# StreamDeck.net
KiCad netlist of a schematic drawn in EAGLE
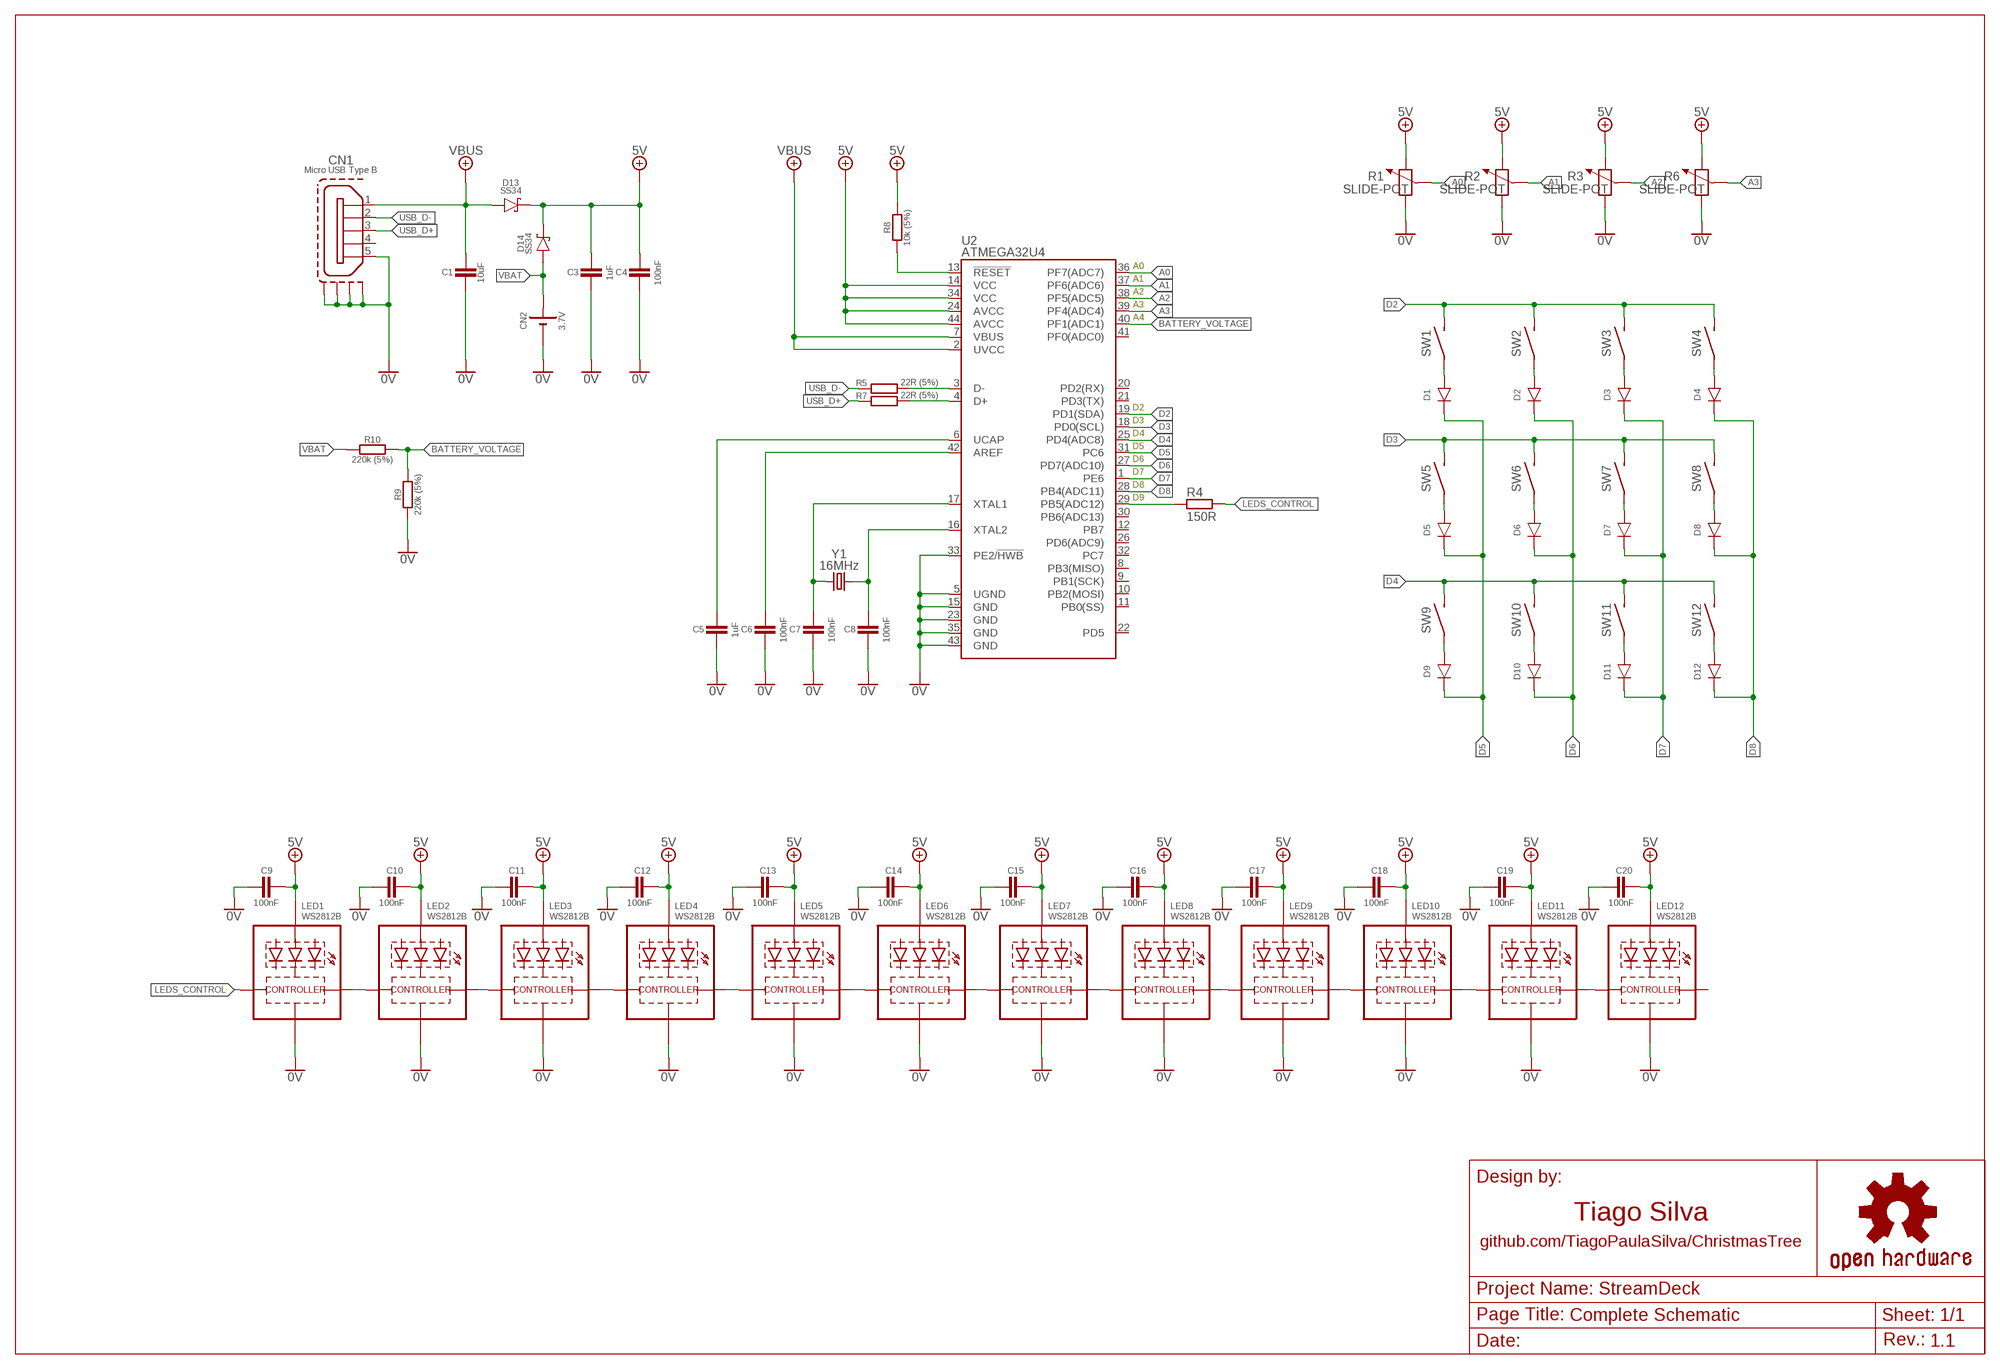
[diagram p0: schematic, sheet 1]

(export (version "E")
  (design (tool "Eeschema 10.0.6"))
  (components
    (comp (ref "C1")
      (value "10uF")
      (footprint "eagle-import:C0805")
      (libsource (lib "eagle-import") (part "C_0805"))
    )
    (comp (ref "C3")
      (value "1uF")
      (footprint "eagle-import:C0603")
      (libsource (lib "eagle-import") (part "C_0603"))
    )
    (comp (ref "C4")
      (value "100nF")
      (footprint "eagle-import:C0603")
      (libsource (lib "eagle-import") (part "C_0603"))
    )
    (comp (ref "C5")
      (value "1uF")
      (footprint "eagle-import:C0603")
      (libsource (lib "eagle-import") (part "C_0603"))
    )
    (comp (ref "C6")
      (value "100nF")
      (footprint "eagle-import:C0603")
      (libsource (lib "eagle-import") (part "C_0603"))
    )
    (comp (ref "C7")
      (value "100nF")
      (footprint "eagle-import:C0603")
      (libsource (lib "eagle-import") (part "C_0603"))
    )
    (comp (ref "C8")
      (value "100nF")
      (footprint "eagle-import:C0603")
      (libsource (lib "eagle-import") (part "C_0603"))
    )
    (comp (ref "C9")
      (value "100nF")
      (footprint "eagle-import:C0603")
      (libsource (lib "eagle-import") (part "C_0603"))
    )
    (comp (ref "C10")
      (value "100nF")
      (footprint "eagle-import:C0603")
      (libsource (lib "eagle-import") (part "C_0603"))
    )
    (comp (ref "C11")
      (value "100nF")
      (footprint "eagle-import:C0603")
      (libsource (lib "eagle-import") (part "C_0603"))
    )
    (comp (ref "C12")
      (value "100nF")
      (footprint "eagle-import:C0603")
      (libsource (lib "eagle-import") (part "C_0603"))
    )
    (comp (ref "C13")
      (value "100nF")
      (footprint "eagle-import:C0603")
      (libsource (lib "eagle-import") (part "C_0603"))
    )
    (comp (ref "C14")
      (value "100nF")
      (footprint "eagle-import:C0603")
      (libsource (lib "eagle-import") (part "C_0603"))
    )
    (comp (ref "C15")
      (value "100nF")
      (footprint "eagle-import:C0603")
      (libsource (lib "eagle-import") (part "C_0603"))
    )
    (comp (ref "C16")
      (value "100nF")
      (footprint "eagle-import:C0603")
      (libsource (lib "eagle-import") (part "C_0603"))
    )
    (comp (ref "C17")
      (value "100nF")
      (footprint "eagle-import:C0603")
      (libsource (lib "eagle-import") (part "C_0603"))
    )
    (comp (ref "C18")
      (value "100nF")
      (footprint "eagle-import:C0603")
      (libsource (lib "eagle-import") (part "C_0603"))
    )
    (comp (ref "C19")
      (value "100nF")
      (footprint "eagle-import:C0603")
      (libsource (lib "eagle-import") (part "C_0603"))
    )
    (comp (ref "C20")
      (value "100nF")
      (footprint "eagle-import:C0603")
      (libsource (lib "eagle-import") (part "C_0603"))
    )
    (comp (ref "CN1")
      (value "Micro USB Type B")
      (footprint "eagle-import:10118193-0001LF")
      (libsource (lib "eagle-import") (part "MICRO-USB"))
    )
    (comp (ref "CN2")
      (value "3.7V")
      (footprint "eagle-import:JST-PH2")
      (libsource (lib "eagle-import") (part "CELL-CONNECTOR"))
    )
    (comp (ref "D1")
      (value "LL4148")
      (footprint "eagle-import:SOD80")
      (libsource (lib "eagle-import") (part "LL4148"))
    )
    (comp (ref "D2")
      (value "LL4148")
      (footprint "eagle-import:SOD80")
      (libsource (lib "eagle-import") (part "LL4148"))
    )
    (comp (ref "D3")
      (value "LL4148")
      (footprint "eagle-import:SOD80")
      (libsource (lib "eagle-import") (part "LL4148"))
    )
    (comp (ref "D4")
      (value "LL4148")
      (footprint "eagle-import:SOD80")
      (libsource (lib "eagle-import") (part "LL4148"))
    )
    (comp (ref "D5")
      (value "LL4148")
      (footprint "eagle-import:SOD80")
      (libsource (lib "eagle-import") (part "LL4148"))
    )
    (comp (ref "D6")
      (value "LL4148")
      (footprint "eagle-import:SOD80")
      (libsource (lib "eagle-import") (part "LL4148"))
    )
    (comp (ref "D7")
      (value "LL4148")
      (footprint "eagle-import:SOD80")
      (libsource (lib "eagle-import") (part "LL4148"))
    )
    (comp (ref "D8")
      (value "LL4148")
      (footprint "eagle-import:SOD80")
      (libsource (lib "eagle-import") (part "LL4148"))
    )
    (comp (ref "D9")
      (value "LL4148")
      (footprint "eagle-import:SOD80")
      (libsource (lib "eagle-import") (part "LL4148"))
    )
    (comp (ref "D10")
      (value "LL4148")
      (footprint "eagle-import:SOD80")
      (libsource (lib "eagle-import") (part "LL4148"))
    )
    (comp (ref "D11")
      (value "LL4148")
      (footprint "eagle-import:SOD80")
      (libsource (lib "eagle-import") (part "LL4148"))
    )
    (comp (ref "D12")
      (value "LL4148")
      (footprint "eagle-import:SOD80")
      (libsource (lib "eagle-import") (part "LL4148"))
    )
    (comp (ref "D13")
      (value "SS34")
      (footprint "eagle-import:DO214AB")
      (libsource (lib "eagle-import") (part "SS34"))
    )
    (comp (ref "D14")
      (value "SS34")
      (footprint "eagle-import:DO214AB")
      (libsource (lib "eagle-import") (part "SS34"))
    )
    (comp (ref "LED1")
      (value "WS2812B")
      (footprint "eagle-import:5050")
      (libsource (lib "eagle-import") (part "WS2812B"))
    )
    (comp (ref "LED2")
      (value "WS2812B")
      (footprint "eagle-import:5050")
      (libsource (lib "eagle-import") (part "WS2812B"))
    )
    (comp (ref "LED3")
      (value "WS2812B")
      (footprint "eagle-import:5050")
      (libsource (lib "eagle-import") (part "WS2812B"))
    )
    (comp (ref "LED4")
      (value "WS2812B")
      (footprint "eagle-import:5050")
      (libsource (lib "eagle-import") (part "WS2812B"))
    )
    (comp (ref "LED5")
      (value "WS2812B")
      (footprint "eagle-import:5050")
      (libsource (lib "eagle-import") (part "WS2812B"))
    )
    (comp (ref "LED6")
      (value "WS2812B")
      (footprint "eagle-import:5050")
      (libsource (lib "eagle-import") (part "WS2812B"))
    )
    (comp (ref "LED7")
      (value "WS2812B")
      (footprint "eagle-import:5050")
      (libsource (lib "eagle-import") (part "WS2812B"))
    )
    (comp (ref "LED8")
      (value "WS2812B")
      (footprint "eagle-import:5050")
      (libsource (lib "eagle-import") (part "WS2812B"))
    )
    (comp (ref "LED9")
      (value "WS2812B")
      (footprint "eagle-import:5050")
      (libsource (lib "eagle-import") (part "WS2812B"))
    )
    (comp (ref "LED10")
      (value "WS2812B")
      (footprint "eagle-import:5050")
      (libsource (lib "eagle-import") (part "WS2812B"))
    )
    (comp (ref "LED11")
      (value "WS2812B")
      (footprint "eagle-import:5050")
      (libsource (lib "eagle-import") (part "WS2812B"))
    )
    (comp (ref "LED12")
      (value "WS2812B")
      (footprint "eagle-import:5050")
      (libsource (lib "eagle-import") (part "WS2812B"))
    )
    (comp (ref "R1")
      (value "SLIDE-POT")
      (footprint "eagle-import:SLIDER-75MM")
      (libsource (lib "eagle-import") (part "SLIDE-POT"))
    )
    (comp (ref "R2")
      (value "SLIDE-POT")
      (footprint "eagle-import:SLIDER-75MM")
      (libsource (lib "eagle-import") (part "SLIDE-POT"))
    )
    (comp (ref "R3")
      (value "SLIDE-POT")
      (footprint "eagle-import:SLIDER-75MM")
      (libsource (lib "eagle-import") (part "SLIDE-POT"))
    )
    (comp (ref "R4")
      (value "150R")
      (footprint "eagle-import:R0603")
      (libsource (lib "eagle-import") (part "R_0603"))
    )
    (comp (ref "R5")
      (value "22R (5%)")
      (footprint "eagle-import:R0603")
      (libsource (lib "eagle-import") (part "R_0603"))
    )
    (comp (ref "R6")
      (value "SLIDE-POT")
      (footprint "eagle-import:SLIDER-75MM")
      (libsource (lib "eagle-import") (part "SLIDE-POT"))
    )
    (comp (ref "R7")
      (value "22R (5%)")
      (footprint "eagle-import:R0603")
      (libsource (lib "eagle-import") (part "R_0603"))
    )
    (comp (ref "R8")
      (value "10k (5%)")
      (footprint "eagle-import:R0603")
      (libsource (lib "eagle-import") (part "R_0603"))
    )
    (comp (ref "R9")
      (value "220k (5%)")
      (footprint "eagle-import:R0603")
      (libsource (lib "eagle-import") (part "R_0603"))
    )
    (comp (ref "R10")
      (value "220k (5%)")
      (footprint "eagle-import:R0603")
      (libsource (lib "eagle-import") (part "R_0603"))
    )
    (comp (ref "SW1")
      (value "CHERRY_MX")
      (footprint "eagle-import:CHERRY-MX")
      (libsource (lib "eagle-import") (part "CHERRY_MX"))
    )
    (comp (ref "SW2")
      (value "CHERRY_MX")
      (footprint "eagle-import:CHERRY-MX")
      (libsource (lib "eagle-import") (part "CHERRY_MX"))
    )
    (comp (ref "SW3")
      (value "CHERRY_MX")
      (footprint "eagle-import:CHERRY-MX")
      (libsource (lib "eagle-import") (part "CHERRY_MX"))
    )
    (comp (ref "SW4")
      (value "CHERRY_MX")
      (footprint "eagle-import:CHERRY-MX")
      (libsource (lib "eagle-import") (part "CHERRY_MX"))
    )
    (comp (ref "SW5")
      (value "CHERRY_MX")
      (footprint "eagle-import:CHERRY-MX")
      (libsource (lib "eagle-import") (part "CHERRY_MX"))
    )
    (comp (ref "SW6")
      (value "CHERRY_MX")
      (footprint "eagle-import:CHERRY-MX")
      (libsource (lib "eagle-import") (part "CHERRY_MX"))
    )
    (comp (ref "SW7")
      (value "CHERRY_MX")
      (footprint "eagle-import:CHERRY-MX")
      (libsource (lib "eagle-import") (part "CHERRY_MX"))
    )
    (comp (ref "SW8")
      (value "CHERRY_MX")
      (footprint "eagle-import:CHERRY-MX")
      (libsource (lib "eagle-import") (part "CHERRY_MX"))
    )
    (comp (ref "SW9")
      (value "CHERRY_MX")
      (footprint "eagle-import:CHERRY-MX")
      (libsource (lib "eagle-import") (part "CHERRY_MX"))
    )
    (comp (ref "SW10")
      (value "CHERRY_MX")
      (footprint "eagle-import:CHERRY-MX")
      (libsource (lib "eagle-import") (part "CHERRY_MX"))
    )
    (comp (ref "SW11")
      (value "CHERRY_MX")
      (footprint "eagle-import:CHERRY-MX")
      (libsource (lib "eagle-import") (part "CHERRY_MX"))
    )
    (comp (ref "SW12")
      (value "CHERRY_MX")
      (footprint "eagle-import:CHERRY-MX")
      (libsource (lib "eagle-import") (part "CHERRY_MX"))
    )
    (comp (ref "U2")
      (value "ATMEGA32U4")
      (footprint "eagle-import:TESTING_QFN-44")
      (libsource (lib "eagle-import") (part "TESTING_ATMEGA32U4QFN"))
    )
    (comp (ref "Y1")
      (value "16MHz")
      (footprint "eagle-import:5.0X3.2_KX-9A")
      (libsource (lib "eagle-import") (part "KX-9A"))
    )
  )
  (nets
    (net (code "1") (name "0V") (class "Default")
      (node (ref "C1") (pin "2") (pinfunction "2_2") (pintype "passive"))
      (node (ref "C10") (pin "2") (pinfunction "2_2") (pintype "passive"))
      (node (ref "C11") (pin "2") (pinfunction "2_2") (pintype "passive"))
      (node (ref "C12") (pin "2") (pinfunction "2_2") (pintype "passive"))
      (node (ref "C13") (pin "2") (pinfunction "2_2") (pintype "passive"))
      (node (ref "C14") (pin "2") (pinfunction "2_2") (pintype "passive"))
      (node (ref "C15") (pin "2") (pinfunction "2_2") (pintype "passive"))
      (node (ref "C16") (pin "2") (pinfunction "2_2") (pintype "passive"))
      (node (ref "C17") (pin "2") (pinfunction "2_2") (pintype "passive"))
      (node (ref "C18") (pin "2") (pinfunction "2_2") (pintype "passive"))
      (node (ref "C19") (pin "2") (pinfunction "2_2") (pintype "passive"))
      (node (ref "C20") (pin "2") (pinfunction "2_2") (pintype "passive"))
      (node (ref "C3") (pin "2") (pinfunction "2_2") (pintype "passive"))
      (node (ref "C4") (pin "2") (pinfunction "2_2") (pintype "passive"))
      (node (ref "C5") (pin "2") (pinfunction "2_2") (pintype "passive"))
      (node (ref "C6") (pin "2") (pinfunction "2_2") (pintype "passive"))
      (node (ref "C7") (pin "2") (pinfunction "2_2") (pintype "passive"))
      (node (ref "C8") (pin "2") (pinfunction "2_2") (pintype "passive"))
      (node (ref "C9") (pin "2") (pinfunction "2_2") (pintype "passive"))
      (node (ref "CN1") (pin "5") (pinfunction "5_5") (pintype "passive"))
      (node (ref "CN1") (pin "MP1") (pinfunction "S1_MP1") (pintype "passive"))
      (node (ref "CN1") (pin "MP2") (pinfunction "S2_MP2") (pintype "passive"))
      (node (ref "CN1") (pin "MP3") (pinfunction "S3_MP3") (pintype "passive"))
      (node (ref "CN1") (pin "MP4") (pinfunction "S4_MP4") (pintype "passive"))
      (node (ref "CN2") (pin "2") (pinfunction "-_2") (pintype "passive"))
      (node (ref "LED1") (pin "3-GND") (pinfunction "GND_3-GND") (pintype "power_in"))
      (node (ref "LED10") (pin "3-GND") (pinfunction "GND_3-GND") (pintype "power_in"))
      (node (ref "LED11") (pin "3-GND") (pinfunction "GND_3-GND") (pintype "power_in"))
      (node (ref "LED12") (pin "3-GND") (pinfunction "GND_3-GND") (pintype "power_in"))
      (node (ref "LED2") (pin "3-GND") (pinfunction "GND_3-GND") (pintype "power_in"))
      (node (ref "LED3") (pin "3-GND") (pinfunction "GND_3-GND") (pintype "power_in"))
      (node (ref "LED4") (pin "3-GND") (pinfunction "GND_3-GND") (pintype "power_in"))
      (node (ref "LED5") (pin "3-GND") (pinfunction "GND_3-GND") (pintype "power_in"))
      (node (ref "LED6") (pin "3-GND") (pinfunction "GND_3-GND") (pintype "power_in"))
      (node (ref "LED7") (pin "3-GND") (pinfunction "GND_3-GND") (pintype "power_in"))
      (node (ref "LED8") (pin "3-GND") (pinfunction "GND_3-GND") (pintype "power_in"))
      (node (ref "LED9") (pin "3-GND") (pinfunction "GND_3-GND") (pintype "power_in"))
      (node (ref "R1") (pin "P$1") (pinfunction "1_P$1") (pintype "passive"))
      (node (ref "R2") (pin "P$1") (pinfunction "1_P$1") (pintype "passive"))
      (node (ref "R3") (pin "P$1") (pinfunction "1_P$1") (pintype "passive"))
      (node (ref "R6") (pin "P$1") (pinfunction "1_P$1") (pintype "passive"))
      (node (ref "R9") (pin "1") (pinfunction "1_1") (pintype "passive"))
      (node (ref "U2") (pin "15") (pinfunction "GND_15") (pintype "bidirectional"))
      (node (ref "U2") (pin "23") (pinfunction "GND_23") (pintype "bidirectional"))
      (node (ref "U2") (pin "33") (pinfunction "PE2/~{HWB}_33") (pintype "bidirectional"))
      (node (ref "U2") (pin "35") (pinfunction "GND_35") (pintype "bidirectional"))
      (node (ref "U2") (pin "43") (pinfunction "GND_43") (pintype "bidirectional"))
      (node (ref "U2") (pin "5") (pinfunction "UGND_5") (pintype "bidirectional"))
    )
    (net (code "2") (name "5V") (class "Default")
      (node (ref "C10") (pin "1") (pinfunction "1_1") (pintype "passive"))
      (node (ref "C11") (pin "1") (pinfunction "1_1") (pintype "passive"))
      (node (ref "C12") (pin "1") (pinfunction "1_1") (pintype "passive"))
      (node (ref "C13") (pin "1") (pinfunction "1_1") (pintype "passive"))
      (node (ref "C14") (pin "1") (pinfunction "1_1") (pintype "passive"))
      (node (ref "C15") (pin "1") (pinfunction "1_1") (pintype "passive"))
      (node (ref "C16") (pin "1") (pinfunction "1_1") (pintype "passive"))
      (node (ref "C17") (pin "1") (pinfunction "1_1") (pintype "passive"))
      (node (ref "C18") (pin "1") (pinfunction "1_1") (pintype "passive"))
      (node (ref "C19") (pin "1") (pinfunction "1_1") (pintype "passive"))
      (node (ref "C20") (pin "1") (pinfunction "1_1") (pintype "passive"))
      (node (ref "C3") (pin "1") (pinfunction "1_1") (pintype "passive"))
      (node (ref "C4") (pin "1") (pinfunction "1_1") (pintype "passive"))
      (node (ref "C9") (pin "1") (pinfunction "1_1") (pintype "passive"))
      (node (ref "D13") (pin "C") (pinfunction "K_C") (pintype "passive"))
      (node (ref "D14") (pin "C") (pinfunction "K_C") (pintype "passive"))
      (node (ref "LED1") (pin "1-VDD") (pinfunction "VDD_1-VDD") (pintype "power_in"))
      (node (ref "LED10") (pin "1-VDD") (pinfunction "VDD_1-VDD") (pintype "power_in"))
      (node (ref "LED11") (pin "1-VDD") (pinfunction "VDD_1-VDD") (pintype "power_in"))
      (node (ref "LED12") (pin "1-VDD") (pinfunction "VDD_1-VDD") (pintype "power_in"))
      (node (ref "LED2") (pin "1-VDD") (pinfunction "VDD_1-VDD") (pintype "power_in"))
      (node (ref "LED3") (pin "1-VDD") (pinfunction "VDD_1-VDD") (pintype "power_in"))
      (node (ref "LED4") (pin "1-VDD") (pinfunction "VDD_1-VDD") (pintype "power_in"))
      (node (ref "LED5") (pin "1-VDD") (pinfunction "VDD_1-VDD") (pintype "power_in"))
      (node (ref "LED6") (pin "1-VDD") (pinfunction "VDD_1-VDD") (pintype "power_in"))
      (node (ref "LED7") (pin "1-VDD") (pinfunction "VDD_1-VDD") (pintype "power_in"))
      (node (ref "LED8") (pin "1-VDD") (pinfunction "VDD_1-VDD") (pintype "power_in"))
      (node (ref "LED9") (pin "1-VDD") (pinfunction "VDD_1-VDD") (pintype "power_in"))
      (node (ref "R1") (pin "P$2") (pinfunction "2_P$2") (pintype "passive"))
      (node (ref "R2") (pin "P$2") (pinfunction "2_P$2") (pintype "passive"))
      (node (ref "R3") (pin "P$2") (pinfunction "2_P$2") (pintype "passive"))
      (node (ref "R6") (pin "P$2") (pinfunction "2_P$2") (pintype "passive"))
      (node (ref "R8") (pin "2") (pinfunction "2_2") (pintype "passive"))
      (node (ref "U2") (pin "14") (pinfunction "VCC_14") (pintype "bidirectional"))
      (node (ref "U2") (pin "24") (pinfunction "AVCC_24") (pintype "bidirectional"))
      (node (ref "U2") (pin "34") (pinfunction "VCC_34") (pintype "bidirectional"))
      (node (ref "U2") (pin "44") (pinfunction "AVCC_44") (pintype "bidirectional"))
    )
    (net (code "3") (name "A0") (class "Default")
      (node (ref "R1") (pin "P$6") (pinfunction "3_P$6") (pintype "passive"))
      (node (ref "U2") (pin "36") (pinfunction "PF7(ADC7)_36") (pintype "bidirectional"))
    )
    (net (code "4") (name "A1") (class "Default")
      (node (ref "R2") (pin "P$6") (pinfunction "3_P$6") (pintype "passive"))
      (node (ref "U2") (pin "37") (pinfunction "PF6(ADC6)_37") (pintype "bidirectional"))
    )
    (net (code "5") (name "A2") (class "Default")
      (node (ref "R3") (pin "P$6") (pinfunction "3_P$6") (pintype "passive"))
      (node (ref "U2") (pin "38") (pinfunction "PF5(ADC5)_38") (pintype "bidirectional"))
    )
    (net (code "6") (name "A3") (class "Default")
      (node (ref "R6") (pin "P$6") (pinfunction "3_P$6") (pintype "passive"))
      (node (ref "U2") (pin "39") (pinfunction "PF4(ADC4)_39") (pintype "bidirectional"))
    )
    (net (code "7") (name "BATTERY_VOLTAGE") (class "Default")
      (node (ref "R10") (pin "2") (pinfunction "2_2") (pintype "passive"))
      (node (ref "R9") (pin "2") (pinfunction "2_2") (pintype "passive"))
      (node (ref "U2") (pin "40") (pinfunction "PF1(ADC1)_40") (pintype "bidirectional"))
    )
    (net (code "8") (name "D2") (class "Default")
      (node (ref "SW1") (pin "SW2") (pinfunction "SW2_SW2") (pintype "passive"))
      (node (ref "SW2") (pin "SW2") (pinfunction "SW2_SW2") (pintype "passive"))
      (node (ref "SW3") (pin "SW2") (pinfunction "SW2_SW2") (pintype "passive"))
      (node (ref "SW4") (pin "SW2") (pinfunction "SW2_SW2") (pintype "passive"))
      (node (ref "U2") (pin "19") (pinfunction "PD1(SDA)_19") (pintype "bidirectional"))
    )
    (net (code "9") (name "D3") (class "Default")
      (node (ref "SW5") (pin "SW2") (pinfunction "SW2_SW2") (pintype "passive"))
      (node (ref "SW6") (pin "SW2") (pinfunction "SW2_SW2") (pintype "passive"))
      (node (ref "SW7") (pin "SW2") (pinfunction "SW2_SW2") (pintype "passive"))
      (node (ref "SW8") (pin "SW2") (pinfunction "SW2_SW2") (pintype "passive"))
      (node (ref "U2") (pin "18") (pinfunction "PD0(SCL)_18") (pintype "bidirectional"))
    )
    (net (code "10") (name "D4") (class "Default")
      (node (ref "SW10") (pin "SW2") (pinfunction "SW2_SW2") (pintype "passive"))
      (node (ref "SW11") (pin "SW2") (pinfunction "SW2_SW2") (pintype "passive"))
      (node (ref "SW12") (pin "SW2") (pinfunction "SW2_SW2") (pintype "passive"))
      (node (ref "SW9") (pin "SW2") (pinfunction "SW2_SW2") (pintype "passive"))
      (node (ref "U2") (pin "25") (pinfunction "PD4(ADC8)_25") (pintype "bidirectional"))
    )
    (net (code "11") (name "D5") (class "Default")
      (node (ref "D1") (pin "1") (pinfunction "K_1") (pintype "passive"))
      (node (ref "D5") (pin "1") (pinfunction "K_1") (pintype "passive"))
      (node (ref "D9") (pin "1") (pinfunction "K_1") (pintype "passive"))
      (node (ref "U2") (pin "31") (pinfunction "PC6_31") (pintype "bidirectional"))
    )
    (net (code "12") (name "D6") (class "Default")
      (node (ref "D10") (pin "1") (pinfunction "K_1") (pintype "passive"))
      (node (ref "D2") (pin "1") (pinfunction "K_1") (pintype "passive"))
      (node (ref "D6") (pin "1") (pinfunction "K_1") (pintype "passive"))
      (node (ref "U2") (pin "27") (pinfunction "PD7(ADC10)_27") (pintype "bidirectional"))
    )
    (net (code "13") (name "D7") (class "Default")
      (node (ref "D11") (pin "1") (pinfunction "K_1") (pintype "passive"))
      (node (ref "D3") (pin "1") (pinfunction "K_1") (pintype "passive"))
      (node (ref "D7") (pin "1") (pinfunction "K_1") (pintype "passive"))
      (node (ref "U2") (pin "1") (pinfunction "PE6_1") (pintype "bidirectional"))
    )
    (net (code "14") (name "D8") (class "Default")
      (node (ref "D12") (pin "1") (pinfunction "K_1") (pintype "passive"))
      (node (ref "D4") (pin "1") (pinfunction "K_1") (pintype "passive"))
      (node (ref "D8") (pin "1") (pinfunction "K_1") (pintype "passive"))
      (node (ref "U2") (pin "28") (pinfunction "PB4(ADC11)_28") (pintype "bidirectional"))
    )
    (net (code "15") (name "LEDS_CONTROL") (class "Default")
      (node (ref "LED1") (pin "4-DIN") (pinfunction "DI_4-DIN") (pintype "input"))
      (node (ref "R4") (pin "2") (pinfunction "2_2") (pintype "passive"))
    )
    (net (code "16") (name "Net-(D1-A)") (class "Default")
      (node (ref "D1") (pin "2") (pinfunction "A_2") (pintype "passive"))
      (node (ref "SW1") (pin "SW1") (pinfunction "SW1_SW1") (pintype "passive"))
    )
    (net (code "17") (name "Net-(D2-A)") (class "Default")
      (node (ref "D2") (pin "2") (pinfunction "A_2") (pintype "passive"))
      (node (ref "SW2") (pin "SW1") (pinfunction "SW1_SW1") (pintype "passive"))
    )
    (net (code "18") (name "Net-(D3-A)") (class "Default")
      (node (ref "D3") (pin "2") (pinfunction "A_2") (pintype "passive"))
      (node (ref "SW3") (pin "SW1") (pinfunction "SW1_SW1") (pintype "passive"))
    )
    (net (code "19") (name "Net-(D4-A)") (class "Default")
      (node (ref "D4") (pin "2") (pinfunction "A_2") (pintype "passive"))
      (node (ref "SW4") (pin "SW1") (pinfunction "SW1_SW1") (pintype "passive"))
    )
    (net (code "20") (name "Net-(D5-A)") (class "Default")
      (node (ref "D5") (pin "2") (pinfunction "A_2") (pintype "passive"))
      (node (ref "SW5") (pin "SW1") (pinfunction "SW1_SW1") (pintype "passive"))
    )
    (net (code "21") (name "Net-(D6-A)") (class "Default")
      (node (ref "D6") (pin "2") (pinfunction "A_2") (pintype "passive"))
      (node (ref "SW6") (pin "SW1") (pinfunction "SW1_SW1") (pintype "passive"))
    )
    (net (code "22") (name "Net-(D7-A)") (class "Default")
      (node (ref "D7") (pin "2") (pinfunction "A_2") (pintype "passive"))
      (node (ref "SW7") (pin "SW1") (pinfunction "SW1_SW1") (pintype "passive"))
    )
    (net (code "23") (name "Net-(D8-A)") (class "Default")
      (node (ref "D8") (pin "2") (pinfunction "A_2") (pintype "passive"))
      (node (ref "SW8") (pin "SW1") (pinfunction "SW1_SW1") (pintype "passive"))
    )
    (net (code "24") (name "Net-(D9-A)") (class "Default")
      (node (ref "D9") (pin "2") (pinfunction "A_2") (pintype "passive"))
      (node (ref "SW9") (pin "SW1") (pinfunction "SW1_SW1") (pintype "passive"))
    )
    (net (code "25") (name "Net-(D10-A)") (class "Default")
      (node (ref "D10") (pin "2") (pinfunction "A_2") (pintype "passive"))
      (node (ref "SW10") (pin "SW1") (pinfunction "SW1_SW1") (pintype "passive"))
    )
    (net (code "26") (name "Net-(D11-A)") (class "Default")
      (node (ref "D11") (pin "2") (pinfunction "A_2") (pintype "passive"))
      (node (ref "SW11") (pin "SW1") (pinfunction "SW1_SW1") (pintype "passive"))
    )
    (net (code "27") (name "Net-(D12-A)") (class "Default")
      (node (ref "D12") (pin "2") (pinfunction "A_2") (pintype "passive"))
      (node (ref "SW12") (pin "SW1") (pinfunction "SW1_SW1") (pintype "passive"))
    )
    (net (code "28") (name "Net-(LED1-DO)") (class "Default")
      (node (ref "LED1") (pin "2-DOUT") (pinfunction "DO_2-DOUT") (pintype "output"))
      (node (ref "LED2") (pin "4-DIN") (pinfunction "DI_4-DIN") (pintype "input"))
    )
    (net (code "29") (name "Net-(LED2-DO)") (class "Default")
      (node (ref "LED2") (pin "2-DOUT") (pinfunction "DO_2-DOUT") (pintype "output"))
      (node (ref "LED3") (pin "4-DIN") (pinfunction "DI_4-DIN") (pintype "input"))
    )
    (net (code "30") (name "Net-(LED3-DO)") (class "Default")
      (node (ref "LED3") (pin "2-DOUT") (pinfunction "DO_2-DOUT") (pintype "output"))
      (node (ref "LED4") (pin "4-DIN") (pinfunction "DI_4-DIN") (pintype "input"))
    )
    (net (code "31") (name "Net-(LED4-DO)") (class "Default")
      (node (ref "LED4") (pin "2-DOUT") (pinfunction "DO_2-DOUT") (pintype "output"))
      (node (ref "LED5") (pin "4-DIN") (pinfunction "DI_4-DIN") (pintype "input"))
    )
    (net (code "32") (name "Net-(LED5-DO)") (class "Default")
      (node (ref "LED5") (pin "2-DOUT") (pinfunction "DO_2-DOUT") (pintype "output"))
      (node (ref "LED6") (pin "4-DIN") (pinfunction "DI_4-DIN") (pintype "input"))
    )
    (net (code "33") (name "Net-(LED6-DO)") (class "Default")
      (node (ref "LED6") (pin "2-DOUT") (pinfunction "DO_2-DOUT") (pintype "output"))
      (node (ref "LED7") (pin "4-DIN") (pinfunction "DI_4-DIN") (pintype "input"))
    )
    (net (code "34") (name "Net-(LED7-DO)") (class "Default")
      (node (ref "LED7") (pin "2-DOUT") (pinfunction "DO_2-DOUT") (pintype "output"))
      (node (ref "LED8") (pin "4-DIN") (pinfunction "DI_4-DIN") (pintype "input"))
    )
    (net (code "35") (name "Net-(LED8-DO)") (class "Default")
      (node (ref "LED8") (pin "2-DOUT") (pinfunction "DO_2-DOUT") (pintype "output"))
      (node (ref "LED9") (pin "4-DIN") (pinfunction "DI_4-DIN") (pintype "input"))
    )
    (net (code "36") (name "Net-(LED10-DI)") (class "Default")
      (node (ref "LED10") (pin "4-DIN") (pinfunction "DI_4-DIN") (pintype "input"))
      (node (ref "LED9") (pin "2-DOUT") (pinfunction "DO_2-DOUT") (pintype "output"))
    )
    (net (code "37") (name "Net-(LED10-DO)") (class "Default")
      (node (ref "LED10") (pin "2-DOUT") (pinfunction "DO_2-DOUT") (pintype "output"))
      (node (ref "LED11") (pin "4-DIN") (pinfunction "DI_4-DIN") (pintype "input"))
    )
    (net (code "38") (name "Net-(LED11-DO)") (class "Default")
      (node (ref "LED11") (pin "2-DOUT") (pinfunction "DO_2-DOUT") (pintype "output"))
      (node (ref "LED12") (pin "4-DIN") (pinfunction "DI_4-DIN") (pintype "input"))
    )
    (net (code "39") (name "Net-(U2-AREF)") (class "Default")
      (node (ref "C6") (pin "1") (pinfunction "1_1") (pintype "passive"))
      (node (ref "U2") (pin "42") (pinfunction "AREF_42") (pintype "bidirectional"))
    )
    (net (code "40") (name "Net-(U2-D+)") (class "Default")
      (node (ref "R7") (pin "2") (pinfunction "2_2") (pintype "passive"))
      (node (ref "U2") (pin "4") (pinfunction "D+_4") (pintype "bidirectional"))
    )
    (net (code "41") (name "Net-(U2-D-)") (class "Default")
      (node (ref "R5") (pin "2") (pinfunction "2_2") (pintype "passive"))
      (node (ref "U2") (pin "3") (pinfunction "D-_3") (pintype "bidirectional"))
    )
    (net (code "42") (name "Net-(U2-PB5(ADC12))") (class "Default")
      (node (ref "R4") (pin "1") (pinfunction "1_1") (pintype "passive"))
      (node (ref "U2") (pin "29") (pinfunction "PB5(ADC12)_29") (pintype "bidirectional"))
    )
    (net (code "43") (name "Net-(U2-UCAP)") (class "Default")
      (node (ref "C5") (pin "1") (pinfunction "1_1") (pintype "passive"))
      (node (ref "U2") (pin "6") (pinfunction "UCAP_6") (pintype "bidirectional"))
    )
    (net (code "44") (name "Net-(U2-XTAL1)") (class "Default")
      (node (ref "C7") (pin "1") (pinfunction "1_1") (pintype "passive"))
      (node (ref "U2") (pin "17") (pinfunction "XTAL1_17") (pintype "bidirectional"))
      (node (ref "Y1") (pin "1") (pinfunction "1_1") (pintype "passive"))
    )
    (net (code "45") (name "Net-(U2-XTAL2)") (class "Default")
      (node (ref "C8") (pin "1") (pinfunction "1_1") (pintype "passive"))
      (node (ref "U2") (pin "16") (pinfunction "XTAL2_16") (pintype "bidirectional"))
      (node (ref "Y1") (pin "3") (pinfunction "2_3") (pintype "passive"))
    )
    (net (code "46") (name "Net-(U2-~{RESET})") (class "Default")
      (node (ref "R8") (pin "1") (pinfunction "1_1") (pintype "passive"))
      (node (ref "U2") (pin "13") (pinfunction "~{RESET}_13") (pintype "bidirectional"))
    )
    (net (code "47") (name "USB_D+") (class "Default")
      (node (ref "CN1") (pin "3") (pinfunction "3_3") (pintype "passive"))
      (node (ref "R7") (pin "1") (pinfunction "1_1") (pintype "passive"))
    )
    (net (code "48") (name "USB_D-") (class "Default")
      (node (ref "CN1") (pin "2") (pinfunction "2_2") (pintype "passive"))
      (node (ref "R5") (pin "1") (pinfunction "1_1") (pintype "passive"))
    )
    (net (code "49") (name "VBAT") (class "Default")
      (node (ref "CN2") (pin "1") (pinfunction "+_1") (pintype "passive"))
      (node (ref "D14") (pin "A") (pinfunction "A_A") (pintype "passive"))
      (node (ref "R10") (pin "1") (pinfunction "1_1") (pintype "passive"))
    )
    (net (code "50") (name "VBUS") (class "Default")
      (node (ref "C1") (pin "1") (pinfunction "1_1") (pintype "passive"))
      (node (ref "CN1") (pin "1") (pinfunction "1_1") (pintype "passive"))
      (node (ref "D13") (pin "A") (pinfunction "A_A") (pintype "passive"))
      (node (ref "U2") (pin "2") (pinfunction "UVCC_2") (pintype "bidirectional"))
      (node (ref "U2") (pin "7") (pinfunction "VBUS_7") (pintype "bidirectional"))
    )
    (net (code "51") (name "unconnected-(CN1-Pad4)") (class "Default")
      (node (ref "CN1") (pin "4") (pinfunction "4_4") (pintype "passive"))
    )
    (net (code "52") (name "unconnected-(LED12-DO-Pad2-DOUT)") (class "Default")
      (node (ref "LED12") (pin "2-DOUT") (pinfunction "DO_2-DOUT") (pintype "output"))
    )
    (net (code "53") (name "unconnected-(U2-PB0(SS)-Pad11)") (class "Default")
      (node (ref "U2") (pin "11") (pinfunction "PB0(SS)_11") (pintype "bidirectional"))
    )
    (net (code "54") (name "unconnected-(U2-PB1(SCK)-Pad9)") (class "Default")
      (node (ref "U2") (pin "9") (pinfunction "PB1(SCK)_9") (pintype "bidirectional"))
    )
    (net (code "55") (name "unconnected-(U2-PB2(MOSI)-Pad10)") (class "Default")
      (node (ref "U2") (pin "10") (pinfunction "PB2(MOSI)_10") (pintype "bidirectional"))
    )
    (net (code "56") (name "unconnected-(U2-PB3(MISO)-Pad8)") (class "Default")
      (node (ref "U2") (pin "8") (pinfunction "PB3(MISO)_8") (pintype "bidirectional"))
    )
    (net (code "57") (name "unconnected-(U2-PB6(ADC13)-Pad30)") (class "Default")
      (node (ref "U2") (pin "30") (pinfunction "PB6(ADC13)_30") (pintype "bidirectional"))
    )
    (net (code "58") (name "unconnected-(U2-PB7-Pad12)") (class "Default")
      (node (ref "U2") (pin "12") (pinfunction "PB7_12") (pintype "bidirectional"))
    )
    (net (code "59") (name "unconnected-(U2-PC7-Pad32)") (class "Default")
      (node (ref "U2") (pin "32") (pinfunction "PC7_32") (pintype "bidirectional"))
    )
    (net (code "60") (name "unconnected-(U2-PD2(RX)-Pad20)") (class "Default")
      (node (ref "U2") (pin "20") (pinfunction "PD2(RX)_20") (pintype "bidirectional"))
    )
    (net (code "61") (name "unconnected-(U2-PD3(TX)-Pad21)") (class "Default")
      (node (ref "U2") (pin "21") (pinfunction "PD3(TX)_21") (pintype "bidirectional"))
    )
    (net (code "62") (name "unconnected-(U2-PD5-Pad22)") (class "Default")
      (node (ref "U2") (pin "22") (pinfunction "PD5_22") (pintype "bidirectional"))
    )
    (net (code "63") (name "unconnected-(U2-PD6(ADC9)-Pad26)") (class "Default")
      (node (ref "U2") (pin "26") (pinfunction "PD6(ADC9)_26") (pintype "bidirectional"))
    )
    (net (code "64") (name "unconnected-(U2-PF0(ADC0)-Pad41)") (class "Default")
      (node (ref "U2") (pin "41") (pinfunction "PF0(ADC0)_41") (pintype "bidirectional"))
    )
  )
)
